# SCH_SmartBluetoothScanner_2022-03-12.net
KiCad netlist of a schematic drawn in EasyEDA
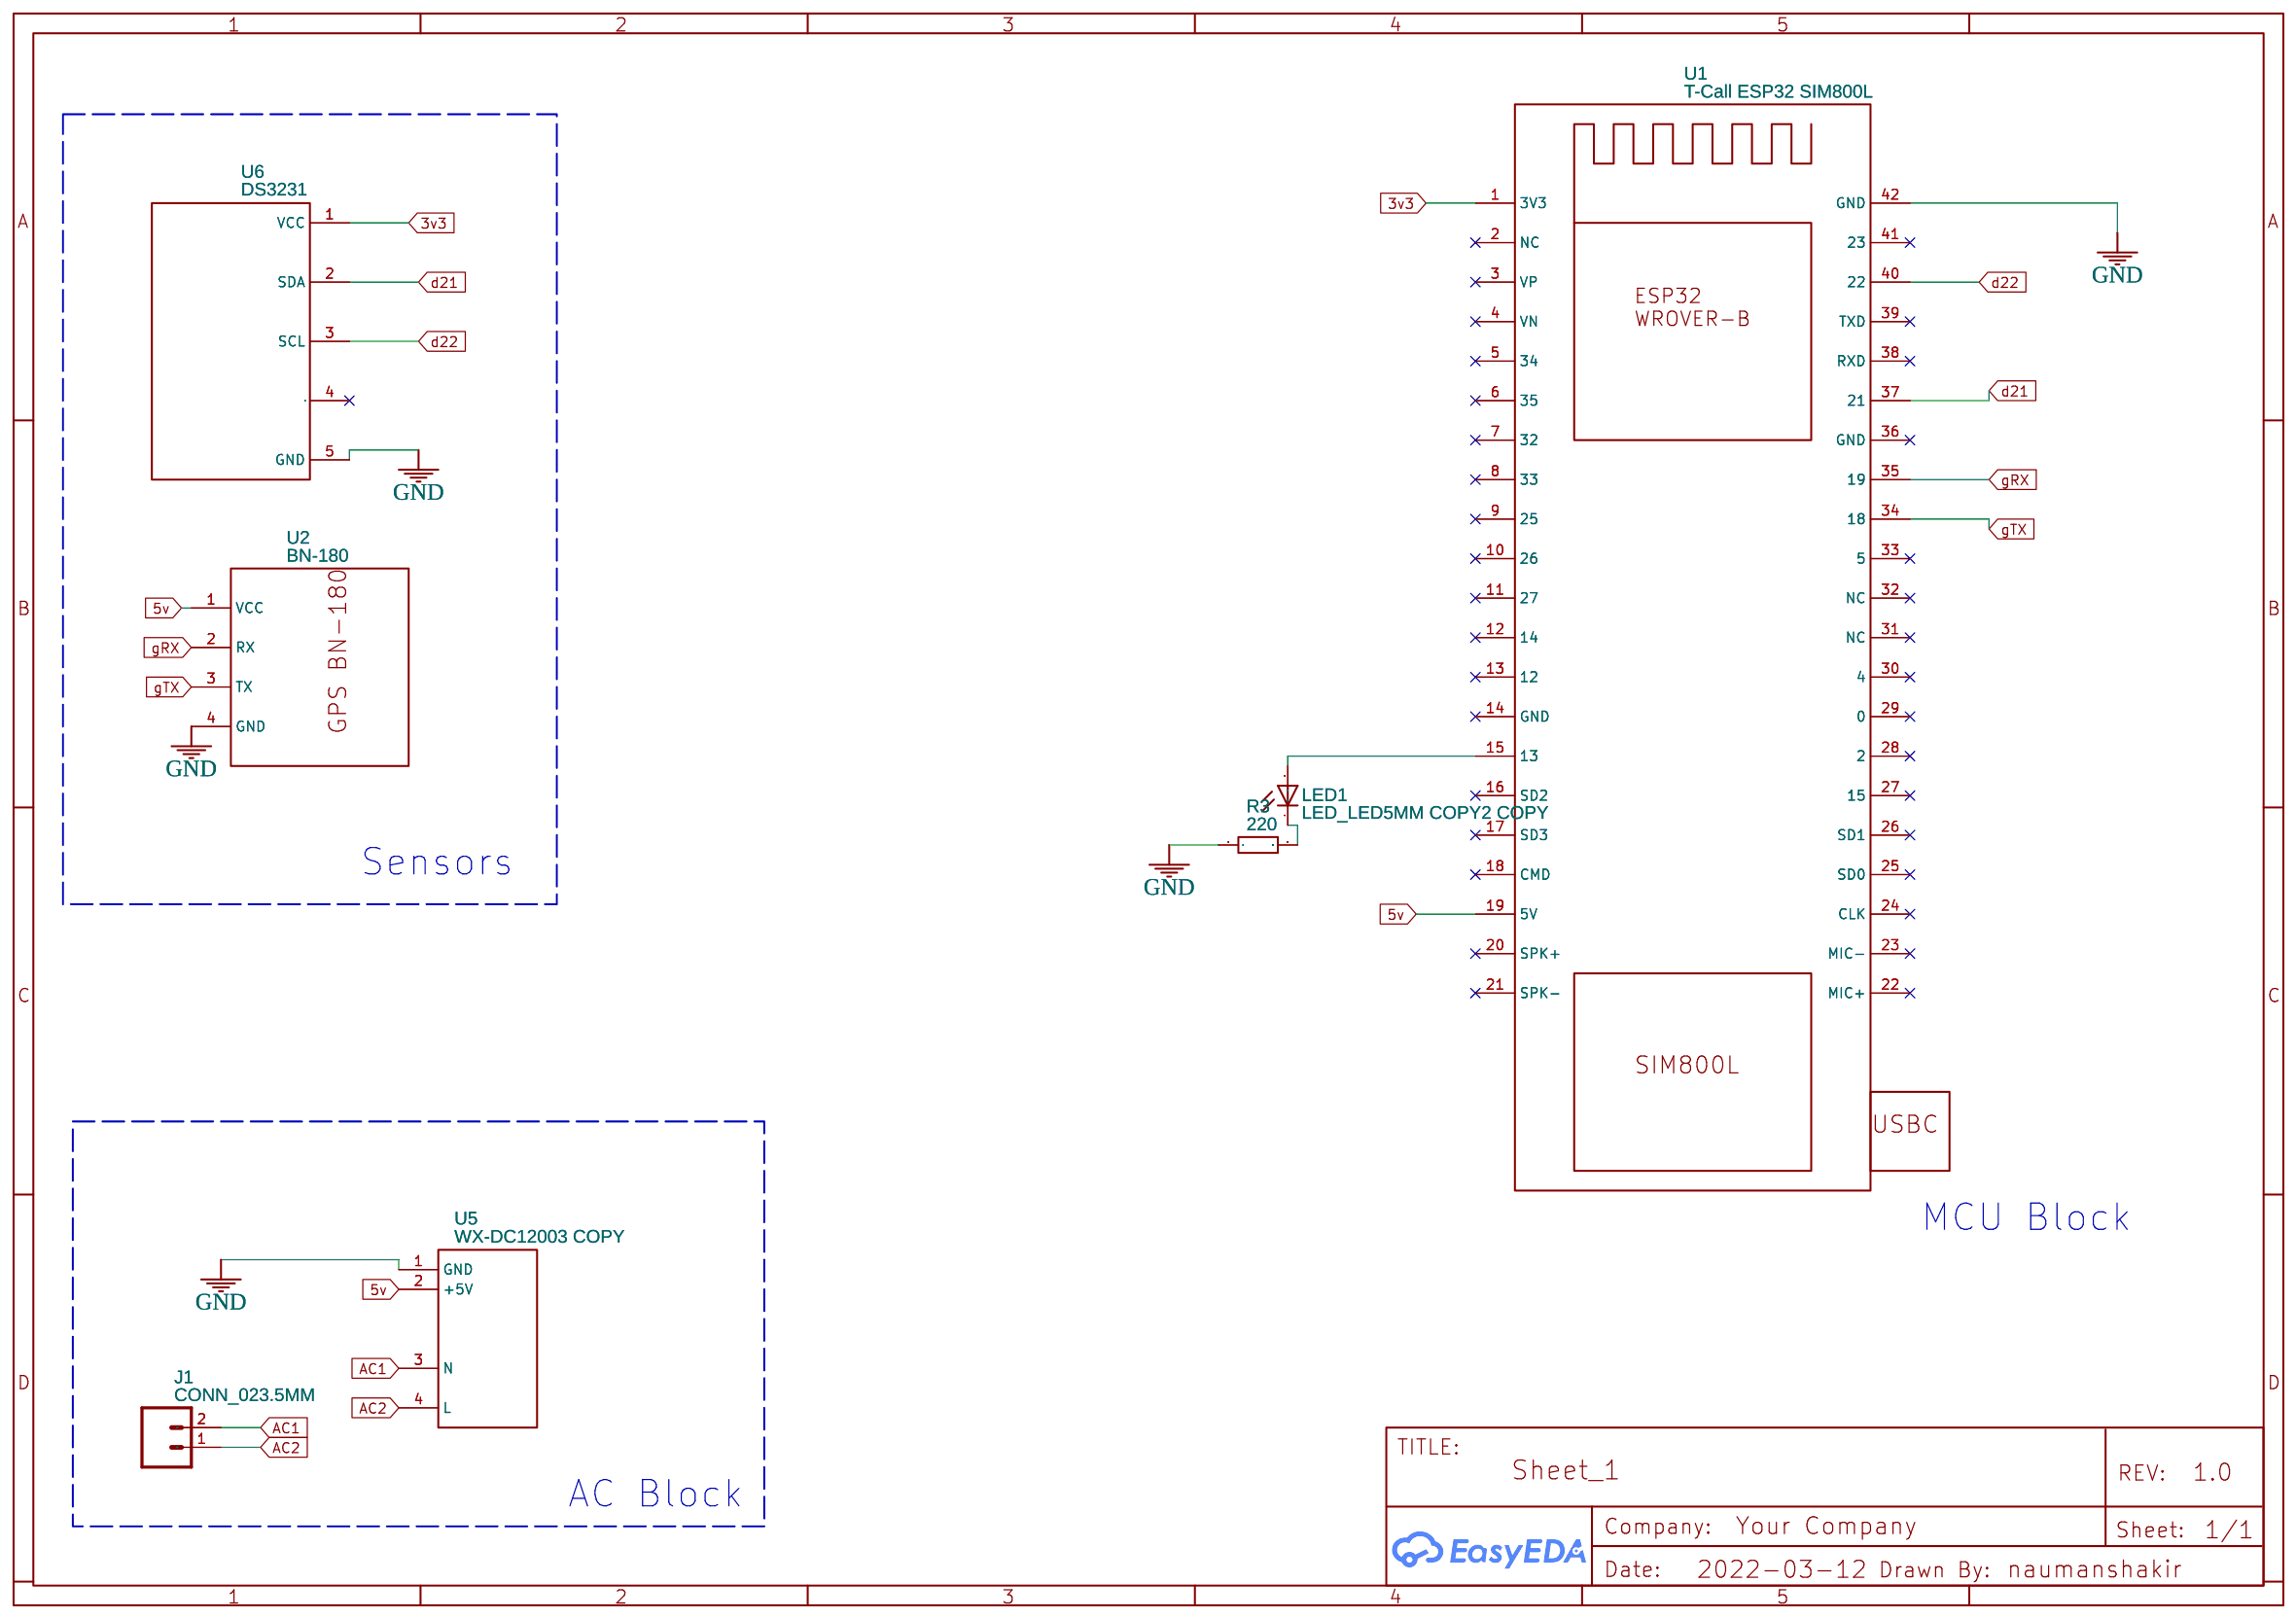
[diagram p0: schematic sheet]

(export (version "E")
  (design (tool "Eeschema 10.0.6"))
  (components
    (comp (ref "J1") (value "CONN_023.5MM") (libsource (lib "") (part "CONN_023.5MM")))
    (comp (ref "LED1") (value "LED_LED5MM COPY2 COPY") (libsource (lib "") (part "LED_LED5MM COPY2 COPY")))
    (comp (ref "R3")
      (value "220")
      (fields
        (field (name "BOM_Manufacturer Part") "RD50T5221J")
        (field (name "BOM_Supplier Part") "C167559")
      )
      (libsource (lib "") (part "RD50T5221J"))
    )
    (comp (ref "U1")
      (value "T-Call ESP32 SIM800L")
      (fields (field (name "BOM_Supplier Part") "ESP32 SIM800L"))
      (libsource (lib "") (part "T-Call ESP32 SIM800L"))
    )
    (comp (ref "U2") (value "BN-180") (libsource (lib "") (part "BN-180")))
    (comp (ref "U5") (value "WX-DC12003 COPY") (libsource (lib "") (part "WX-DC12003 COPY")))
    (comp (ref "U6")
      (value "DS3231")
      (fields (field (name "BOM_Manufacturer Part") "New SchematicLib"))
      (libsource (lib "") (part "DS3231"))
    )
  )
  (nets
    (net (code "1") (name "3v3") (class "Default")
      (node (ref "U1") (pin "1") (pinfunction "3V3_1") (pintype "unspecified"))
      (node (ref "U6") (pin "1") (pinfunction "VCC_1") (pintype "unspecified"))
    )
    (net (code "2") (name "5v") (class "Default")
      (node (ref "U1") (pin "19") (pinfunction "5V_19") (pintype "unspecified"))
      (node (ref "U2") (pin "1") (pinfunction "VCC_1") (pintype "unspecified"))
      (node (ref "U5") (pin "2") (pinfunction "+5V_2") (pintype "unspecified"))
    )
    (net (code "3") (name "AC1") (class "Default")
      (node (ref "J1") (pin "2") (pinfunction "2_2") (pintype "bidirectional"))
      (node (ref "U5") (pin "3") (pinfunction "N_3") (pintype "unspecified"))
    )
    (net (code "4") (name "AC2") (class "Default")
      (node (ref "J1") (pin "1") (pinfunction "1_1") (pintype "bidirectional"))
      (node (ref "U5") (pin "4") (pinfunction "L_4") (pintype "unspecified"))
    )
    (net (code "5") (name "GND") (class "Default")
      (node (ref "R3") (pin "1") (pinfunction "1_1") (pintype "unspecified"))
      (node (ref "U1") (pin "42") (pinfunction "GND_42") (pintype "unspecified"))
      (node (ref "U2") (pin "4") (pinfunction "GND_4") (pintype "unspecified"))
      (node (ref "U5") (pin "1") (pinfunction "GND_1") (pintype "unspecified"))
      (node (ref "U6") (pin "5") (pinfunction "GND_5") (pintype "unspecified"))
    )
    (net (code "6") (name "Net-(LED1-C)") (class "Default")
      (node (ref "LED1") (pin "K") (pinfunction "C_K") (pintype "unspecified"))
      (node (ref "R3") (pin "2") (pinfunction "2_2") (pintype "unspecified"))
    )
    (net (code "7") (name "Net-(U1-13)") (class "Default")
      (node (ref "LED1") (pin "A") (pinfunction "A_A") (pintype "unspecified"))
      (node (ref "U1") (pin "15") (pinfunction "13_15") (pintype "unspecified"))
    )
    (net (code "8") (name "d21") (class "Default")
      (node (ref "U1") (pin "37") (pinfunction "21_37") (pintype "unspecified"))
      (node (ref "U6") (pin "2") (pinfunction "SDA_2") (pintype "unspecified"))
    )
    (net (code "9") (name "d22") (class "Default")
      (node (ref "U1") (pin "40") (pinfunction "22_40") (pintype "unspecified"))
      (node (ref "U6") (pin "3") (pinfunction "SCL_3") (pintype "unspecified"))
    )
    (net (code "10") (name "gRX") (class "Default")
      (node (ref "U1") (pin "35") (pinfunction "19_35") (pintype "unspecified"))
      (node (ref "U2") (pin "2") (pinfunction "RX_2") (pintype "unspecified"))
    )
    (net (code "11") (name "gTX") (class "Default")
      (node (ref "U1") (pin "34") (pinfunction "18_34") (pintype "unspecified"))
      (node (ref "U2") (pin "3") (pinfunction "TX_3") (pintype "unspecified"))
    )
    (net (code "12") (name "unconnected-(U1-0-Pad29)") (class "Default")
      (node (ref "U1") (pin "29") (pinfunction "0_29") (pintype "unspecified+no_connect"))
    )
    (net (code "13") (name "unconnected-(U1-2-Pad28)") (class "Default")
      (node (ref "U1") (pin "28") (pinfunction "2_28") (pintype "unspecified+no_connect"))
    )
    (net (code "14") (name "unconnected-(U1-4-Pad30)") (class "Default")
      (node (ref "U1") (pin "30") (pinfunction "4_30") (pintype "unspecified+no_connect"))
    )
    (net (code "15") (name "unconnected-(U1-5-Pad33)") (class "Default")
      (node (ref "U1") (pin "33") (pinfunction "5_33") (pintype "unspecified+no_connect"))
    )
    (net (code "16") (name "unconnected-(U1-12-Pad13)") (class "Default")
      (node (ref "U1") (pin "13") (pinfunction "12_13") (pintype "unspecified+no_connect"))
    )
    (net (code "17") (name "unconnected-(U1-14-Pad12)") (class "Default")
      (node (ref "U1") (pin "12") (pinfunction "14_12") (pintype "unspecified+no_connect"))
    )
    (net (code "18") (name "unconnected-(U1-15-Pad27)") (class "Default")
      (node (ref "U1") (pin "27") (pinfunction "15_27") (pintype "unspecified+no_connect"))
    )
    (net (code "19") (name "unconnected-(U1-23-Pad41)") (class "Default")
      (node (ref "U1") (pin "41") (pinfunction "23_41") (pintype "unspecified+no_connect"))
    )
    (net (code "20") (name "unconnected-(U1-25-Pad9)") (class "Default")
      (node (ref "U1") (pin "9") (pinfunction "25_9") (pintype "unspecified+no_connect"))
    )
    (net (code "21") (name "unconnected-(U1-26-Pad10)") (class "Default")
      (node (ref "U1") (pin "10") (pinfunction "26_10") (pintype "unspecified+no_connect"))
    )
    (net (code "22") (name "unconnected-(U1-27-Pad11)") (class "Default")
      (node (ref "U1") (pin "11") (pinfunction "27_11") (pintype "unspecified+no_connect"))
    )
    (net (code "23") (name "unconnected-(U1-32-Pad7)") (class "Default")
      (node (ref "U1") (pin "7") (pinfunction "32_7") (pintype "unspecified+no_connect"))
    )
    (net (code "24") (name "unconnected-(U1-33-Pad8)") (class "Default")
      (node (ref "U1") (pin "8") (pinfunction "33_8") (pintype "unspecified+no_connect"))
    )
    (net (code "25") (name "unconnected-(U1-34-Pad5)") (class "Default")
      (node (ref "U1") (pin "5") (pinfunction "34_5") (pintype "unspecified+no_connect"))
    )
    (net (code "26") (name "unconnected-(U1-35-Pad6)") (class "Default")
      (node (ref "U1") (pin "6") (pinfunction "35_6") (pintype "unspecified+no_connect"))
    )
    (net (code "27") (name "unconnected-(U1-CLK-Pad24)") (class "Default")
      (node (ref "U1") (pin "24") (pinfunction "CLK_24") (pintype "unspecified+no_connect"))
    )
    (net (code "28") (name "unconnected-(U1-CMD-Pad18)") (class "Default")
      (node (ref "U1") (pin "18") (pinfunction "CMD_18") (pintype "unspecified+no_connect"))
    )
    (net (code "29") (name "unconnected-(U1-GND-Pad14)") (class "Default")
      (node (ref "U1") (pin "14") (pinfunction "GND_14") (pintype "unspecified+no_connect"))
    )
    (net (code "30") (name "unconnected-(U1-GND-Pad36)") (class "Default")
      (node (ref "U1") (pin "36") (pinfunction "GND_36") (pintype "unspecified+no_connect"))
    )
    (net (code "31") (name "unconnected-(U1-MIC+-Pad22)") (class "Default")
      (node (ref "U1") (pin "22") (pinfunction "MIC+_22") (pintype "unspecified+no_connect"))
    )
    (net (code "32") (name "unconnected-(U1-MIC--Pad23)") (class "Default")
      (node (ref "U1") (pin "23") (pinfunction "MIC-_23") (pintype "unspecified+no_connect"))
    )
    (net (code "33") (name "unconnected-(U1-NC-Pad2)") (class "Default")
      (node (ref "U1") (pin "2") (pinfunction "NC_2") (pintype "unspecified+no_connect"))
    )
    (net (code "34") (name "unconnected-(U1-NC-Pad31)") (class "Default")
      (node (ref "U1") (pin "31") (pinfunction "NC_31") (pintype "unspecified+no_connect"))
    )
    (net (code "35") (name "unconnected-(U1-NC-Pad32)") (class "Default")
      (node (ref "U1") (pin "32") (pinfunction "NC_32") (pintype "unspecified+no_connect"))
    )
    (net (code "36") (name "unconnected-(U1-RXD-Pad38)") (class "Default")
      (node (ref "U1") (pin "38") (pinfunction "RXD_38") (pintype "unspecified+no_connect"))
    )
    (net (code "37") (name "unconnected-(U1-SD0-Pad25)") (class "Default")
      (node (ref "U1") (pin "25") (pinfunction "SD0_25") (pintype "unspecified+no_connect"))
    )
    (net (code "38") (name "unconnected-(U1-SD1-Pad26)") (class "Default")
      (node (ref "U1") (pin "26") (pinfunction "SD1_26") (pintype "unspecified+no_connect"))
    )
    (net (code "39") (name "unconnected-(U1-SD2-Pad16)") (class "Default")
      (node (ref "U1") (pin "16") (pinfunction "SD2_16") (pintype "unspecified+no_connect"))
    )
    (net (code "40") (name "unconnected-(U1-SD3-Pad17)") (class "Default")
      (node (ref "U1") (pin "17") (pinfunction "SD3_17") (pintype "unspecified+no_connect"))
    )
    (net (code "41") (name "unconnected-(U1-SPK+-Pad20)") (class "Default")
      (node (ref "U1") (pin "20") (pinfunction "SPK+_20") (pintype "unspecified+no_connect"))
    )
    (net (code "42") (name "unconnected-(U1-SPK--Pad21)") (class "Default")
      (node (ref "U1") (pin "21") (pinfunction "SPK-_21") (pintype "unspecified+no_connect"))
    )
    (net (code "43") (name "unconnected-(U1-TXD-Pad39)") (class "Default")
      (node (ref "U1") (pin "39") (pinfunction "TXD_39") (pintype "unspecified+no_connect"))
    )
    (net (code "44") (name "unconnected-(U1-VN-Pad4)") (class "Default")
      (node (ref "U1") (pin "4") (pinfunction "VN_4") (pintype "unspecified+no_connect"))
    )
    (net (code "45") (name "unconnected-(U1-VP-Pad3)") (class "Default")
      (node (ref "U1") (pin "3") (pinfunction "VP_3") (pintype "unspecified+no_connect"))
    )
    (net (code "46") (name "unconnected-(U6-Pad4)") (class "Default")
      (node (ref "U6") (pin "4") (pinfunction "4_4") (pintype "unspecified+no_connect"))
    )
  )
)
